# Isolation.net
KiCad netlist of a schematic drawn in EAGLE
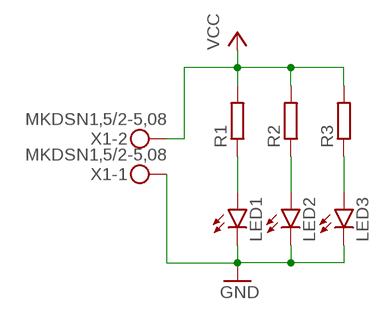
[diagram p0: schematic, sheet 1]

(export (version "E")
  (design (tool "Eeschema 10.0.6"))
  (components
    (comp (ref "LED1")
      (value "LED5MM")
      (footprint "eagle-import:LED5MM")
      (libsource (lib "eagle-import") (part "LED5MM"))
    )
    (comp (ref "LED2")
      (value "LED5MM")
      (footprint "eagle-import:LED5MM")
      (libsource (lib "eagle-import") (part "LED5MM"))
    )
    (comp (ref "LED3")
      (value "LED5MM")
      (footprint "eagle-import:LED5MM")
      (libsource (lib "eagle-import") (part "LED5MM"))
    )
    (comp (ref "R1")
      (value "R-EU_0204/7")
      (footprint "eagle-import:0204_7")
      (libsource (lib "eagle-import") (part "R-EU_0204/7"))
    )
    (comp (ref "R2")
      (value "R-EU_0204/7")
      (footprint "eagle-import:0204_7")
      (libsource (lib "eagle-import") (part "R-EU_0204/7"))
    )
    (comp (ref "R3")
      (value "R-EU_0204/7")
      (footprint "eagle-import:0204_7")
      (libsource (lib "eagle-import") (part "R-EU_0204/7"))
    )
    (comp (ref "X1")
      (value "MKDSN1,5/2-5,08")
      (footprint "eagle-import:MKDSN1,5_2-5,08")
      (libsource (lib "eagle-import") (part "MKDSN1,5/2-5,08"))
    )
  )
  (nets
    (net (code "1") (name "GND") (class "Default")
      (node (ref "LED1") (pin "K") (pinfunction "C_K") (pintype "passive"))
      (node (ref "LED2") (pin "K") (pinfunction "C_K") (pintype "passive"))
      (node (ref "LED3") (pin "K") (pinfunction "C_K") (pintype "passive"))
      (node (ref "X1") (pin "1") (pinfunction "KL_1") (pintype "passive"))
    )
    (net (code "2") (name "Net-(LED1-PadA)") (class "Default")
      (node (ref "LED1") (pin "A") (pinfunction "A_A") (pintype "passive"))
      (node (ref "R1") (pin "1") (pinfunction "1_1") (pintype "passive"))
    )
    (net (code "3") (name "Net-(LED2-PadA)") (class "Default")
      (node (ref "LED2") (pin "A") (pinfunction "A_A") (pintype "passive"))
      (node (ref "R2") (pin "1") (pinfunction "1_1") (pintype "passive"))
    )
    (net (code "4") (name "Net-(LED3-PadA)") (class "Default")
      (node (ref "LED3") (pin "A") (pinfunction "A_A") (pintype "passive"))
      (node (ref "R3") (pin "1") (pinfunction "1_1") (pintype "passive"))
    )
    (net (code "5") (name "VCC") (class "Default")
      (node (ref "R1") (pin "2") (pinfunction "2_2") (pintype "passive"))
      (node (ref "R2") (pin "2") (pinfunction "2_2") (pintype "passive"))
      (node (ref "R3") (pin "2") (pinfunction "2_2") (pintype "passive"))
      (node (ref "X1") (pin "2") (pinfunction "KL_2") (pintype "passive"))
    )
  )
)
